# touch_board.net
KiCad netlist of a schematic drawn in EAGLE
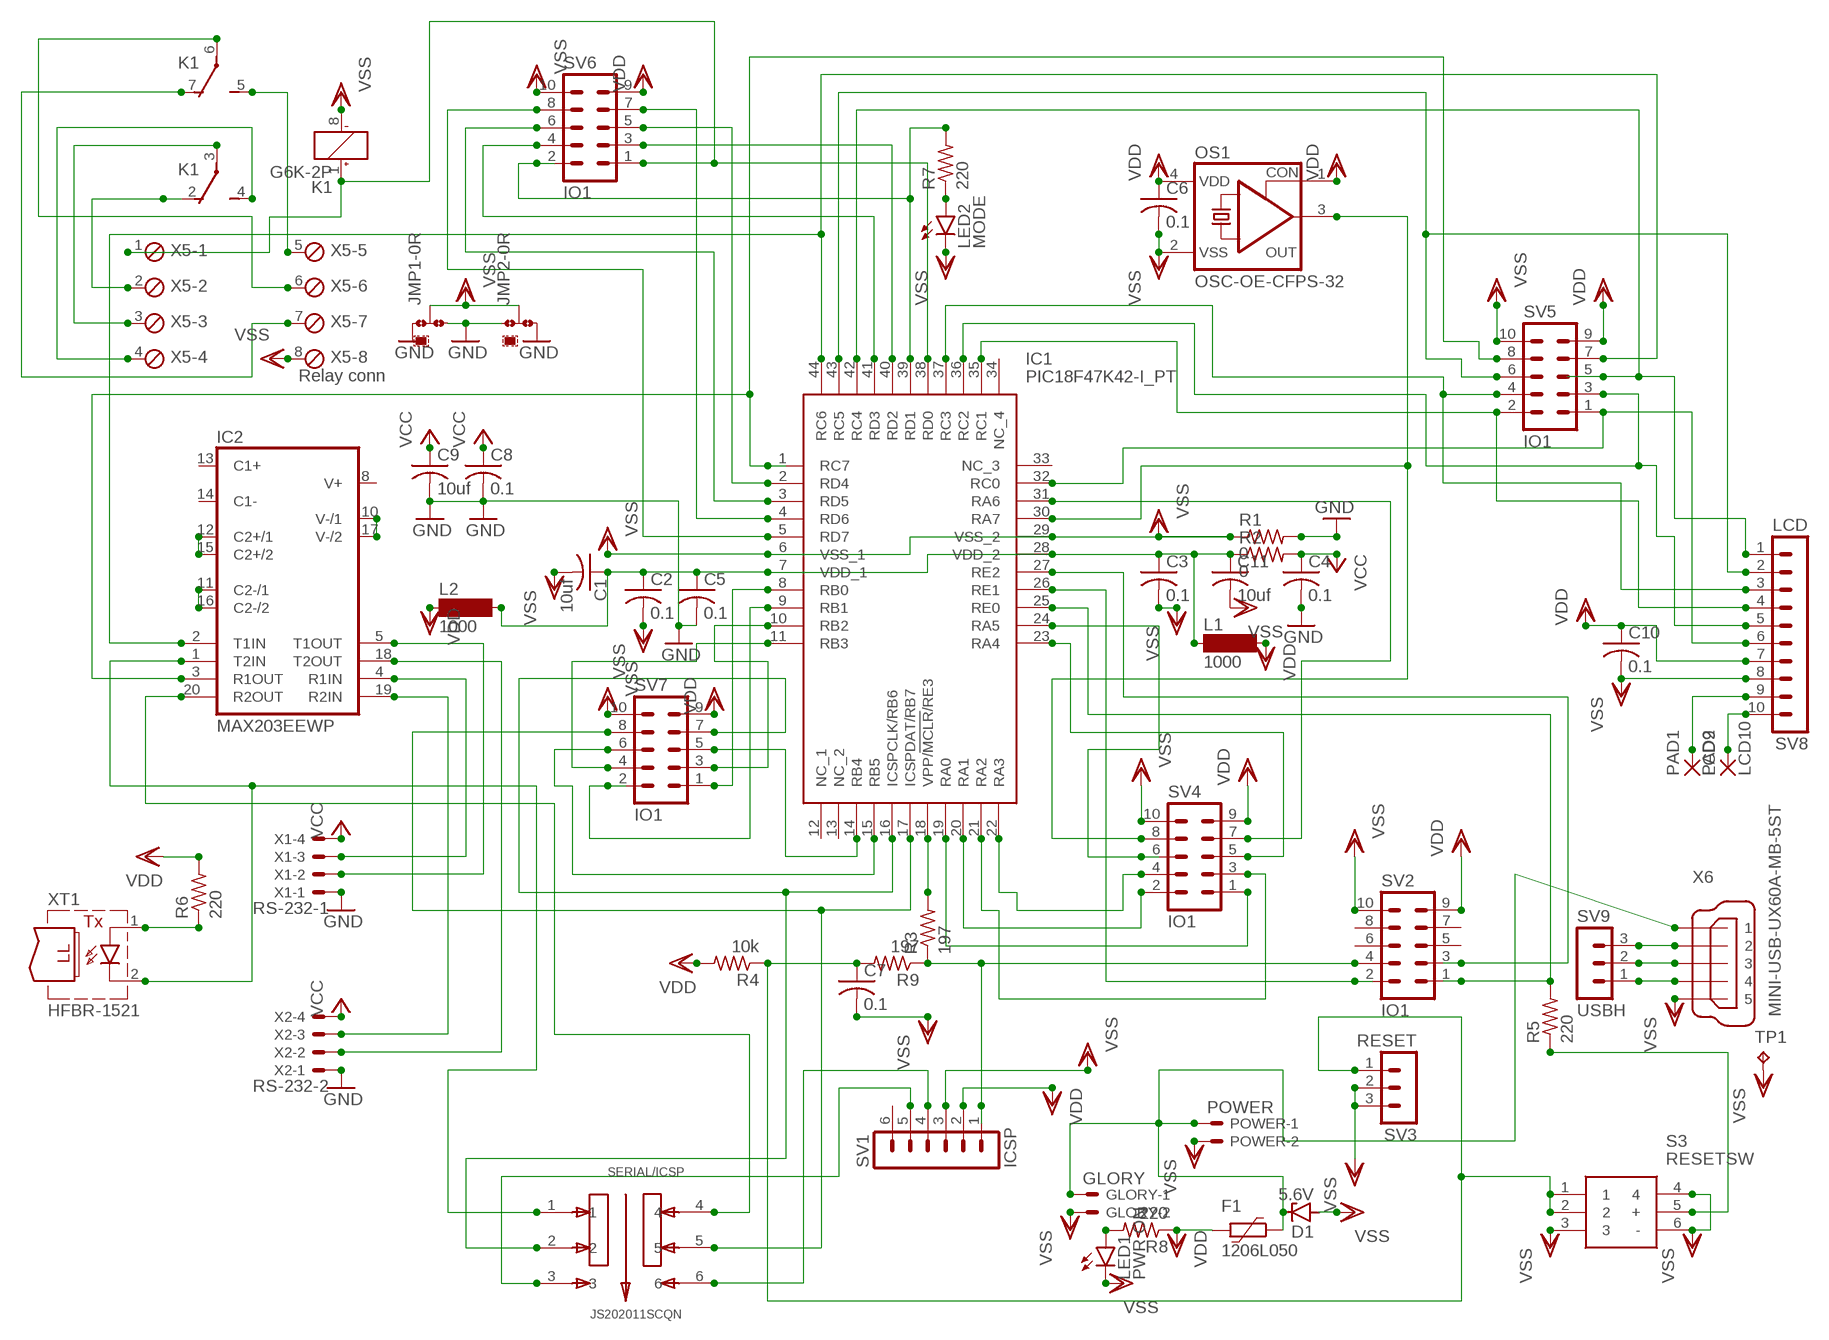
[diagram p0: schematic, sheet 1]

(export (version "E")
  (design (tool "Eeschema 10.0.6"))
  (components
    (comp (ref "C1")
      (value "10uf")
      (footprint "eagle-import:C0805")
      (libsource (lib "eagle-import") (part "C-USC0805"))
    )
    (comp (ref "C2")
      (value "0.1")
      (footprint "eagle-import:C0805")
      (libsource (lib "eagle-import") (part "C-USC0805"))
    )
    (comp (ref "C3")
      (value "0.1")
      (footprint "eagle-import:C0805")
      (libsource (lib "eagle-import") (part "C-USC0805"))
    )
    (comp (ref "C4")
      (value "0.1")
      (footprint "eagle-import:C0805")
      (libsource (lib "eagle-import") (part "C-USC0805"))
    )
    (comp (ref "C5")
      (value "0.1")
      (footprint "eagle-import:C0805")
      (libsource (lib "eagle-import") (part "C-USC0805"))
    )
    (comp (ref "C6")
      (value "0.1")
      (footprint "eagle-import:C0805")
      (libsource (lib "eagle-import") (part "C-USC0805"))
    )
    (comp (ref "C7")
      (value "0.1")
      (footprint "eagle-import:C0805")
      (libsource (lib "eagle-import") (part "C-USC0805"))
    )
    (comp (ref "C8")
      (value "0.1")
      (footprint "eagle-import:C0805")
      (libsource (lib "eagle-import") (part "C-USC0805"))
    )
    (comp (ref "C9")
      (value "10uf")
      (footprint "eagle-import:C0805")
      (libsource (lib "eagle-import") (part "C-USC0805"))
    )
    (comp (ref "C10")
      (value "0.1")
      (footprint "eagle-import:C0805")
      (libsource (lib "eagle-import") (part "C-USC0805"))
    )
    (comp (ref "C11")
      (value "10uf")
      (footprint "eagle-import:C0805")
      (libsource (lib "eagle-import") (part "C-USC0805"))
    )
    (comp (ref "D1")
      (value "5.6V")
      (footprint "eagle-import:ZDIO-7.5")
      (libsource (lib "eagle-import") (part "ZENER-DIODEZD-7.5"))
    )
    (comp (ref "F1")
      (value "1206L050")
      (footprint "eagle-import:1206L")
      (fields (field (name "MF") "Littelfuse"))
      (libsource (lib "eagle-import") (part "?1206L050"))
    )
    (comp (ref "GLORY")
      (value "GLORY")
      (footprint "eagle-import:22-23-2021")
      (fields (field (name "MF") "MOLEX") (field (name "MPN") "22-23-2021"))
      (libsource (lib "eagle-import") (part "22-23-2021"))
    )
    (comp (ref "IC1")
      (value "PIC18F47K42-I_PT")
      (footprint "eagle-import:QFP80P1200X1200X120-44N")
      (fields
        (field (name "MANUFACTURER_PART_NUMBER") "PIC18F47K42-I/PT")
        (field (name "MOUSER_PART_NUMBER") "579-PIC18F47K42-I/PT")
      )
      (libsource (lib "eagle-import") (part "PIC18F47K42-I_PT"))
    )
    (comp (ref "IC2")
      (value "MAX203EEWP")
      (footprint "eagle-import:SO20L")
      (libsource (lib "eagle-import") (part "MAX203WPEE"))
    )
    (comp (ref "JMP1")
      (value "0R-JUMPA")
      (footprint "eagle-import:A0R-JMP")
      (libsource (lib "eagle-import") (part "0R-JUMPA"))
    )
    (comp (ref "JMP2")
      (value "0R-JUMPA")
      (footprint "eagle-import:A0R-JMP")
      (libsource (lib "eagle-import") (part "0R-JUMPA"))
    )
    (comp (ref "K1")
      (value "G6K-2P")
      (footprint "eagle-import:G6K-2P")
      (fields (field (name "MF") "OMRON COMPONENTS USA") (field (name "MPN") "G6K-2P DC3"))
      (libsource (lib "eagle-import") (part "G6K-2P"))
    )
    (comp (ref "L1")
      (value "1000")
      (footprint "eagle-import:SM-1206")
      (libsource (lib "eagle-import") (part "SM-1206"))
    )
    (comp (ref "L2")
      (value "1000")
      (footprint "eagle-import:SM-1206")
      (libsource (lib "eagle-import") (part "SM-1206"))
    )
    (comp (ref "LED1")
      (value "PWR ON")
      (footprint "eagle-import:CHIPLED_1206")
      (libsource (lib "eagle-import") (part "LEDCHIPLED_1206"))
    )
    (comp (ref "LED2")
      (value "MODE")
      (footprint "eagle-import:CHIPLED_1206")
      (libsource (lib "eagle-import") (part "LEDCHIPLED_1206"))
    )
    (comp (ref "OS1")
      (value "OSC-OE-CFPS-32")
      (footprint "eagle-import:7.2X5.2-4-PAD")
      (libsource (lib "eagle-import") (part "OSC-OE-CFPS-32"))
    )
    (comp (ref "PAD1")
      (value "LCD9")
      (footprint "eagle-import:SMD1,27-2,54")
      (libsource (lib "eagle-import") (part "SMD2"))
    )
    (comp (ref "PAD2")
      (value "LCD10")
      (footprint "eagle-import:SMD1,27-2,54")
      (libsource (lib "eagle-import") (part "SMD2"))
    )
    (comp (ref "POWER")
      (value "POWER")
      (footprint "eagle-import:22-23-2021")
      (fields (field (name "MF") "MOLEX") (field (name "MPN") "22-23-2021"))
      (libsource (lib "eagle-import") (part "22-23-2021"))
    )
    (comp (ref "R1")
      (value "0")
      (footprint "eagle-import:R0805")
      (libsource (lib "eagle-import") (part "R-US_R0805"))
    )
    (comp (ref "R2")
      (value "0")
      (footprint "eagle-import:R0805")
      (libsource (lib "eagle-import") (part "R-US_R0805"))
    )
    (comp (ref "R3")
      (value "197")
      (footprint "eagle-import:R0805")
      (libsource (lib "eagle-import") (part "R-US_R0805"))
    )
    (comp (ref "R4")
      (value "10k")
      (footprint "eagle-import:R0805")
      (libsource (lib "eagle-import") (part "R-US_R0805"))
    )
    (comp (ref "R5")
      (value "220")
      (footprint "eagle-import:R0805")
      (libsource (lib "eagle-import") (part "R-US_R0805"))
    )
    (comp (ref "R6")
      (value "220")
      (footprint "eagle-import:R0805")
      (libsource (lib "eagle-import") (part "R-US_R0805"))
    )
    (comp (ref "R7")
      (value "220")
      (footprint "eagle-import:R0805")
      (libsource (lib "eagle-import") (part "R-US_R0805"))
    )
    (comp (ref "R8")
      (value "220")
      (footprint "eagle-import:R0805")
      (libsource (lib "eagle-import") (part "R-US_R0805"))
    )
    (comp (ref "R9")
      (value "197")
      (footprint "eagle-import:R0805")
      (libsource (lib "eagle-import") (part "R-US_R0805"))
    )
    (comp (ref "S3")
      (value "RESETSW")
      (footprint "eagle-import:B3W-9_1-LED")
      (fields
        (field (name "MANUFACTURER_PART_NUMBER") "B3W-9000-Y1N")
        (field (name "MOUSER_PART_NUMBER") "653-B3W-9000-Y1N")
        (field (name "RS_PART_NUMBER") "0492777P")
      )
      (libsource (lib "eagle-import") (part "B3W-9000-Y1N"))
    )
    (comp (ref "SERIAL/ICSP")
      (value "JS202011SCQN")
      (footprint "eagle-import:SW_JS202011SCQN")
      (fields (field (name "MF") "C&K"))
      (libsource (lib "eagle-import") (part "JS202011SCQN"))
    )
    (comp (ref "SV1")
      (value "ICSP")
      (footprint "eagle-import:MA06-1")
      (libsource (lib "eagle-import") (part "MA06-1"))
    )
    (comp (ref "SV2")
      (value "IO1")
      (footprint "eagle-import:MA05-2")
      (libsource (lib "eagle-import") (part "MA05-2"))
    )
    (comp (ref "SV3")
      (value "RESET")
      (footprint "eagle-import:MA03-1")
      (libsource (lib "eagle-import") (part "MA03-1"))
    )
    (comp (ref "SV4")
      (value "IO1")
      (footprint "eagle-import:MA05-2")
      (libsource (lib "eagle-import") (part "MA05-2"))
    )
    (comp (ref "SV5")
      (value "IO1")
      (footprint "eagle-import:MA05-2")
      (libsource (lib "eagle-import") (part "MA05-2"))
    )
    (comp (ref "SV6")
      (value "IO1")
      (footprint "eagle-import:MA05-2")
      (libsource (lib "eagle-import") (part "MA05-2"))
    )
    (comp (ref "SV7")
      (value "IO1")
      (footprint "eagle-import:MA05-2")
      (libsource (lib "eagle-import") (part "MA05-2"))
    )
    (comp (ref "SV8")
      (value "LCD")
      (footprint "eagle-import:MA10-1")
      (libsource (lib "eagle-import") (part "MA10-1"))
    )
    (comp (ref "SV9")
      (value "USBH")
      (footprint "eagle-import:MA03-1")
      (libsource (lib "eagle-import") (part "MA03-1"))
    )
    (comp (ref "TP1")
      (value "TPB1,27")
      (footprint "eagle-import:B1,27")
      (libsource (lib "eagle-import") (part "TPB1,27"))
    )
    (comp (ref "X1")
      (value "RS-232-1")
      (footprint "eagle-import:22-23-2041")
      (fields (field (name "MF") "MOLEX") (field (name "MPN") "22-23-2041"))
      (libsource (lib "eagle-import") (part "22-23-2041"))
    )
    (comp (ref "X2")
      (value "RS-232-2")
      (footprint "eagle-import:22-23-2041")
      (fields (field (name "MF") "MOLEX") (field (name "MPN") "22-23-2041"))
      (libsource (lib "eagle-import") (part "22-23-2041"))
    )
    (comp (ref "X5")
      (value "Relay conn")
      (footprint "eagle-import:8POL254")
      (libsource (lib "eagle-import") (part "MPT8"))
    )
    (comp (ref "X6")
      (value "MINI-USB-UX60A-MB-5ST")
      (footprint "eagle-import:UX60A-MB-5ST")
      (libsource (lib "eagle-import") (part "MINI-USB-UX60A-MB-5ST"))
    )
    (comp (ref "XT1")
      (value "HFBR-1521")
      (footprint "eagle-import:HFBR-15X3")
      (fields (field (name "MF") "AGILENT TECHNOLOGIES"))
      (libsource (lib "eagle-import") (part "HFBR-1521"))
    )
  )
  (nets
    (net (code "1") (name "GND") (class "Default")
      (node (ref "C4") (pin "2") (pinfunction "2_2") (pintype "passive"))
      (node (ref "C5") (pin "2") (pinfunction "2_2") (pintype "passive"))
      (node (ref "C8") (pin "2") (pinfunction "2_2") (pintype "passive"))
      (node (ref "C9") (pin "2") (pinfunction "2_2") (pintype "passive"))
      (node (ref "JMP1") (pin "1") (pinfunction "1_1") (pintype "passive"))
      (node (ref "JMP1") (pin "3") (pinfunction "3_3") (pintype "passive"))
      (node (ref "JMP2") (pin "1") (pinfunction "1_1") (pintype "passive"))
      (node (ref "JMP2") (pin "3") (pinfunction "3_3") (pintype "passive"))
      (node (ref "R1") (pin "2") (pinfunction "2_2") (pintype "passive"))
      (node (ref "X1") (pin "1") (pinfunction "S_1") (pintype "passive"))
      (node (ref "X2") (pin "1") (pinfunction "S_1") (pintype "passive"))
    )
    (net (code "2") (name "Net-(C7-Pad1)") (class "Default")
      (node (ref "C7") (pin "1") (pinfunction "1_1") (pintype "passive"))
      (node (ref "R4") (pin "1") (pinfunction "1_1") (pintype "passive"))
      (node (ref "R9") (pin "2") (pinfunction "2_2") (pintype "passive"))
      (node (ref "S3") (pin "1") (pinfunction "1_1") (pintype "bidirectional"))
      (node (ref "S3") (pin "2") (pinfunction "2_2") (pintype "bidirectional"))
      (node (ref "SV3") (pin "1") (pinfunction "1_1") (pintype "passive"))
    )
    (net (code "3") (name "Net-(GLORYA-S)") (class "Default")
      (node (ref "D1") (pin "C") (pinfunction "C_C") (pintype "passive"))
      (node (ref "F1") (pin "1") (pinfunction "1_1") (pintype "passive"))
      (node (ref "GLORY") (pin "1") (pinfunction "S_1") (pintype "passive"))
      (node (ref "POWER") (pin "1") (pinfunction "S_1") (pintype "passive"))
      (node (ref "X6") (pin "1") (pinfunction "1_1") (pintype "input"))
    )
    (net (code "4") (name "Net-(IC1-ICSPCLK{slash}RB6)") (class "Default")
      (node (ref "IC1") (pin "16") (pinfunction "ICSPCLK/RB6_16") (pintype "bidirectional"))
      (node (ref "SERIAL/ICSP") (pin "2") (pinfunction "2_2") (pintype "passive"))
      (node (ref "SV7") (pin "7") (pinfunction "7_7") (pintype "passive"))
    )
    (net (code "5") (name "Net-(IC1-ICSPDAT{slash}RB7)") (class "Default")
      (node (ref "IC1") (pin "17") (pinfunction "ICSPDAT/RB7_17") (pintype "bidirectional"))
      (node (ref "SERIAL/ICSP") (pin "5") (pinfunction "5_5") (pintype "passive"))
      (node (ref "SV7") (pin "8") (pinfunction "8_8") (pintype "passive"))
    )
    (net (code "6") (name "Net-(IC1-RA0)") (class "Default")
      (node (ref "IC1") (pin "19") (pinfunction "RA0_19") (pintype "bidirectional"))
      (node (ref "SV4") (pin "1") (pinfunction "1_1") (pintype "passive"))
    )
    (net (code "7") (name "Net-(IC1-RA1)") (class "Default")
      (node (ref "IC1") (pin "20") (pinfunction "RA1_20") (pintype "bidirectional"))
      (node (ref "SV4") (pin "2") (pinfunction "2_2") (pintype "passive"))
    )
    (net (code "8") (name "Net-(IC1-RA2)") (class "Default")
      (node (ref "IC1") (pin "21") (pinfunction "RA2_21") (pintype "bidirectional"))
      (node (ref "SV4") (pin "3") (pinfunction "3_3") (pintype "passive"))
    )
    (net (code "9") (name "Net-(IC1-RA3)") (class "Default")
      (node (ref "IC1") (pin "22") (pinfunction "RA3_22") (pintype "bidirectional"))
      (node (ref "SV4") (pin "4") (pinfunction "4_4") (pintype "passive"))
    )
    (net (code "10") (name "Net-(IC1-RA4)") (class "Default")
      (node (ref "IC1") (pin "23") (pinfunction "RA4_23") (pintype "bidirectional"))
      (node (ref "SV4") (pin "5") (pinfunction "5_5") (pintype "passive"))
    )
    (net (code "11") (name "Net-(IC1-RA5)") (class "Default")
      (node (ref "IC1") (pin "24") (pinfunction "RA5_24") (pintype "bidirectional"))
      (node (ref "SV4") (pin "6") (pinfunction "6_6") (pintype "passive"))
    )
    (net (code "12") (name "Net-(IC1-RA6)") (class "Default")
      (node (ref "IC1") (pin "31") (pinfunction "RA6_31") (pintype "bidirectional"))
      (node (ref "SV4") (pin "7") (pinfunction "7_7") (pintype "passive"))
    )
    (net (code "13") (name "Net-(IC1-RA7)") (class "Default")
      (node (ref "IC1") (pin "30") (pinfunction "RA7_30") (pintype "bidirectional"))
      (node (ref "OS1") (pin "3") (pinfunction "OUT_3") (pintype "output"))
      (node (ref "SV4") (pin "8") (pinfunction "8_8") (pintype "passive"))
    )
    (net (code "14") (name "Net-(IC1-RB0)") (class "Default")
      (node (ref "IC1") (pin "8") (pinfunction "RB0_8") (pintype "bidirectional"))
      (node (ref "SV7") (pin "1") (pinfunction "1_1") (pintype "passive"))
    )
    (net (code "15") (name "Net-(IC1-RB1)") (class "Default")
      (node (ref "IC1") (pin "9") (pinfunction "RB1_9") (pintype "bidirectional"))
      (node (ref "SV7") (pin "2") (pinfunction "2_2") (pintype "passive"))
    )
    (net (code "16") (name "Net-(IC1-RB2)") (class "Default")
      (node (ref "IC1") (pin "10") (pinfunction "RB2_10") (pintype "bidirectional"))
      (node (ref "SV7") (pin "3") (pinfunction "3_3") (pintype "passive"))
    )
    (net (code "17") (name "Net-(IC1-RB3)") (class "Default")
      (node (ref "IC1") (pin "11") (pinfunction "RB3_11") (pintype "bidirectional"))
      (node (ref "SV7") (pin "4") (pinfunction "4_4") (pintype "passive"))
    )
    (net (code "18") (name "Net-(IC1-RB4)") (class "Default")
      (node (ref "IC1") (pin "14") (pinfunction "RB4_14") (pintype "bidirectional"))
      (node (ref "SV7") (pin "5") (pinfunction "5_5") (pintype "passive"))
    )
    (net (code "19") (name "Net-(IC1-RB5)") (class "Default")
      (node (ref "IC1") (pin "15") (pinfunction "RB5_15") (pintype "bidirectional"))
      (node (ref "SV7") (pin "6") (pinfunction "6_6") (pintype "passive"))
    )
    (net (code "20") (name "Net-(IC1-RC0)") (class "Default")
      (node (ref "IC1") (pin "32") (pinfunction "RC0_32") (pintype "bidirectional"))
      (node (ref "SV5") (pin "1") (pinfunction "1_1") (pintype "passive"))
      (node (ref "SV8") (pin "6") (pinfunction "6_6") (pintype "passive"))
    )
    (net (code "21") (name "Net-(IC1-RC1)") (class "Default")
      (node (ref "IC1") (pin "35") (pinfunction "RC1_35") (pintype "bidirectional"))
      (node (ref "SV5") (pin "2") (pinfunction "2_2") (pintype "passive"))
      (node (ref "SV8") (pin "4") (pinfunction "4_4") (pintype "passive"))
    )
    (net (code "22") (name "Net-(IC1-RC2)") (class "Default")
      (node (ref "IC1") (pin "36") (pinfunction "RC2_36") (pintype "bidirectional"))
      (node (ref "SV5") (pin "3") (pinfunction "3_3") (pintype "passive"))
      (node (ref "SV8") (pin "5") (pinfunction "5_5") (pintype "passive"))
    )
    (net (code "23") (name "Net-(IC1-RC3)") (class "Default")
      (node (ref "IC1") (pin "37") (pinfunction "RC3_37") (pintype "bidirectional"))
      (node (ref "SV5") (pin "4") (pinfunction "4_4") (pintype "passive"))
      (node (ref "SV8") (pin "3") (pinfunction "3_3") (pintype "passive"))
    )
    (net (code "24") (name "Net-(IC1-RC4)") (class "Default")
      (node (ref "IC1") (pin "42") (pinfunction "RC4_42") (pintype "bidirectional"))
      (node (ref "SV5") (pin "5") (pinfunction "5_5") (pintype "passive"))
      (node (ref "SV8") (pin "1") (pinfunction "1_1") (pintype "passive"))
    )
    (net (code "25") (name "Net-(IC1-RC5)") (class "Default")
      (node (ref "IC1") (pin "43") (pinfunction "RC5_43") (pintype "bidirectional"))
      (node (ref "SV5") (pin "6") (pinfunction "6_6") (pintype "passive"))
      (node (ref "SV8") (pin "2") (pinfunction "2_2") (pintype "passive"))
    )
    (net (code "26") (name "Net-(IC1-RC6)") (class "Default")
      (node (ref "IC1") (pin "44") (pinfunction "RC6_44") (pintype "bidirectional"))
      (node (ref "IC2") (pin "2") (pinfunction "T1IN_2") (pintype "input"))
      (node (ref "SV5") (pin "7") (pinfunction "7_7") (pintype "passive"))
    )
    (net (code "27") (name "Net-(IC1-RC7)") (class "Default")
      (node (ref "IC1") (pin "1") (pinfunction "RC7_1") (pintype "bidirectional"))
      (node (ref "IC2") (pin "3") (pinfunction "R1OUT_3") (pintype "output"))
      (node (ref "SV5") (pin "8") (pinfunction "8_8") (pintype "passive"))
    )
    (net (code "28") (name "Net-(IC1-RD0)") (class "Default")
      (node (ref "IC1") (pin "38") (pinfunction "RD0_38") (pintype "bidirectional"))
      (node (ref "K1") (pin "1") (pinfunction "+_1") (pintype "passive"))
      (node (ref "SV6") (pin "1") (pinfunction "1_1") (pintype "passive"))
      (node (ref "X5") (pin "1") (pinfunction "1_1") (pintype "passive"))
    )
    (net (code "29") (name "Net-(IC1-RD1)") (class "Default")
      (node (ref "IC1") (pin "39") (pinfunction "RD1_39") (pintype "bidirectional"))
      (node (ref "R7") (pin "2") (pinfunction "2_2") (pintype "passive"))
      (node (ref "SV6") (pin "2") (pinfunction "2_2") (pintype "passive"))
    )
    (net (code "30") (name "Net-(IC1-RD2)") (class "Default")
      (node (ref "IC1") (pin "40") (pinfunction "RD2_40") (pintype "bidirectional"))
      (node (ref "SV6") (pin "3") (pinfunction "3_3") (pintype "passive"))
    )
    (net (code "31") (name "Net-(IC1-RD3)") (class "Default")
      (node (ref "IC1") (pin "41") (pinfunction "RD3_41") (pintype "bidirectional"))
      (node (ref "SV6") (pin "4") (pinfunction "4_4") (pintype "passive"))
    )
    (net (code "32") (name "Net-(IC1-RD4)") (class "Default")
      (node (ref "IC1") (pin "2") (pinfunction "RD4_2") (pintype "bidirectional"))
      (node (ref "SV6") (pin "5") (pinfunction "5_5") (pintype "passive"))
    )
    (net (code "33") (name "Net-(IC1-RD5)") (class "Default")
      (node (ref "IC1") (pin "3") (pinfunction "RD5_3") (pintype "bidirectional"))
      (node (ref "SV6") (pin "6") (pinfunction "6_6") (pintype "passive"))
    )
    (net (code "34") (name "Net-(IC1-RD6)") (class "Default")
      (node (ref "IC1") (pin "4") (pinfunction "RD6_4") (pintype "bidirectional"))
      (node (ref "SV6") (pin "7") (pinfunction "7_7") (pintype "passive"))
    )
    (net (code "35") (name "Net-(IC1-RD7)") (class "Default")
      (node (ref "IC1") (pin "5") (pinfunction "RD7_5") (pintype "bidirectional"))
      (node (ref "SV6") (pin "8") (pinfunction "8_8") (pintype "passive"))
    )
    (net (code "36") (name "Net-(IC1-RE0)") (class "Default")
      (node (ref "IC1") (pin "25") (pinfunction "RE0_25") (pintype "bidirectional"))
      (node (ref "R5") (pin "2") (pinfunction "2_2") (pintype "passive"))
      (node (ref "SV2") (pin "1") (pinfunction "1_1") (pintype "passive"))
    )
    (net (code "37") (name "Net-(IC1-RE1)") (class "Default")
      (node (ref "IC1") (pin "26") (pinfunction "RE1_26") (pintype "bidirectional"))
      (node (ref "SV2") (pin "2") (pinfunction "2_2") (pintype "passive"))
    )
    (net (code "38") (name "Net-(IC1-RE2)") (class "Default")
      (node (ref "IC1") (pin "27") (pinfunction "RE2_27") (pintype "bidirectional"))
      (node (ref "SV2") (pin "3") (pinfunction "3_3") (pintype "passive"))
    )
    (net (code "39") (name "Net-(IC1-VDD_1)") (class "Default")
      (node (ref "C1") (pin "1") (pinfunction "1_1") (pintype "passive"))
      (node (ref "C11") (pin "1") (pinfunction "1_1") (pintype "passive"))
      (node (ref "C2") (pin "1") (pinfunction "1_1") (pintype "passive"))
      (node (ref "C3") (pin "1") (pinfunction "1_1") (pintype "passive"))
      (node (ref "C5") (pin "1") (pinfunction "1_1") (pintype "passive"))
      (node (ref "IC1") (pin "28") (pinfunction "VDD_2_28") (pintype "bidirectional"))
      (node (ref "IC1") (pin "7") (pinfunction "VDD_1_7") (pintype "bidirectional"))
      (node (ref "L1") (pin "1") (pinfunction "1_1") (pintype "passive"))
      (node (ref "L2") (pin "2") (pinfunction "2_2") (pintype "passive"))
      (node (ref "R2") (pin "1") (pinfunction "1_1") (pintype "passive"))
    )
    (net (code "40") (name "Net-(IC1-VPP{slash}~{MCLR}{slash}RE3)") (class "Default")
      (node (ref "IC1") (pin "18") (pinfunction "VPP/~{MCLR}/RE3_18") (pintype "bidirectional"))
      (node (ref "R3") (pin "2") (pinfunction "2_2") (pintype "passive"))
    )
    (net (code "41") (name "Net-(IC2A-C2+{slash}1)") (class "Default")
      (node (ref "IC2") (pin "12") (pinfunction "C2+/1_12") (pintype "passive"))
      (node (ref "IC2") (pin "15") (pinfunction "C2+/2_15") (pintype "passive"))
    )
    (net (code "42") (name "Net-(IC2A-C2-{slash}1)") (class "Default")
      (node (ref "IC2") (pin "11") (pinfunction "C2-/1_11") (pintype "passive"))
      (node (ref "IC2") (pin "16") (pinfunction "C2-/2_16") (pintype "passive"))
    )
    (net (code "43") (name "Net-(IC2A-R1IN)") (class "Default")
      (node (ref "IC2") (pin "4") (pinfunction "R1IN_4") (pintype "input"))
      (node (ref "X1") (pin "3") (pinfunction "S_3") (pintype "passive"))
    )
    (net (code "44") (name "Net-(IC2A-R2IN)") (class "Default")
      (node (ref "IC2") (pin "19") (pinfunction "R2IN_19") (pintype "input"))
      (node (ref "X2") (pin "3") (pinfunction "S_3") (pintype "passive"))
    )
    (net (code "45") (name "Net-(IC2A-R2OUT)") (class "Default")
      (node (ref "IC2") (pin "20") (pinfunction "R2OUT_20") (pintype "output"))
      (node (ref "SERIAL/ICSP") (pin "4") (pinfunction "4_4") (pintype "passive"))
    )
    (net (code "46") (name "Net-(IC2A-T1OUT)") (class "Default")
      (node (ref "IC2") (pin "5") (pinfunction "T1OUT_5") (pintype "output"))
      (node (ref "X1") (pin "2") (pinfunction "S_2") (pintype "passive"))
    )
    (net (code "47") (name "Net-(IC2A-T2IN)") (class "Default")
      (node (ref "IC2") (pin "1") (pinfunction "T2IN_1") (pintype "input"))
      (node (ref "SERIAL/ICSP") (pin "1") (pinfunction "1_1") (pintype "passive"))
      (node (ref "XT1") (pin "2") (pinfunction "C_2") (pintype "passive"))
    )
    (net (code "48") (name "Net-(IC2A-T2OUT)") (class "Default")
      (node (ref "IC2") (pin "18") (pinfunction "T2OUT_18") (pintype "output"))
      (node (ref "X2") (pin "2") (pinfunction "S_2") (pintype "passive"))
    )
    (net (code "49") (name "Net-(IC2A-V-{slash}1)") (class "Default")
      (node (ref "IC2") (pin "10") (pinfunction "V-/1_10") (pintype "passive"))
      (node (ref "IC2") (pin "17") (pinfunction "V-/2_17") (pintype "passive"))
    )
    (net (code "50") (name "Net-(K1B-O)") (class "Default")
      (node (ref "K1") (pin "2") (pinfunction "O_2") (pintype "passive"))
      (node (ref "X5") (pin "2") (pinfunction "1_2") (pintype "passive"))
    )
    (net (code "51") (name "Net-(K1B-P)") (class "Default")
      (node (ref "K1") (pin "3") (pinfunction "P_3") (pintype "passive"))
      (node (ref "X5") (pin "3") (pinfunction "1_3") (pintype "passive"))
    )
    (net (code "52") (name "Net-(K1B-S)") (class "Default")
      (node (ref "K1") (pin "4") (pinfunction "S_4") (pintype "passive"))
      (node (ref "X5") (pin "4") (pinfunction "1_4") (pintype "passive"))
    )
    (net (code "53") (name "Net-(K1C-O)") (class "Default")
      (node (ref "K1") (pin "7") (pinfunction "O_7") (pintype "passive"))
      (node (ref "X5") (pin "7") (pinfunction "1_7") (pintype "passive"))
    )
    (net (code "54") (name "Net-(K1C-P)") (class "Default")
      (node (ref "K1") (pin "6") (pinfunction "P_6") (pintype "passive"))
      (node (ref "X5") (pin "6") (pinfunction "1_6") (pintype "passive"))
    )
    (net (code "55") (name "Net-(K1C-S)") (class "Default")
      (node (ref "K1") (pin "5") (pinfunction "S_5") (pintype "passive"))
      (node (ref "X5") (pin "5") (pinfunction "1_5") (pintype "passive"))
    )
    (net (code "56") (name "Net-(LED1-PadA)") (class "Default")
      (node (ref "LED1") (pin "A") (pinfunction "A_A") (pintype "passive"))
      (node (ref "R8") (pin "2") (pinfunction "2_2") (pintype "passive"))
    )
    (net (code "57") (name "Net-(LED2-PadA)") (class "Default")
      (node (ref "LED2") (pin "A") (pinfunction "A_A") (pintype "passive"))
      (node (ref "R7") (pin "1") (pinfunction "1_1") (pintype "passive"))
    )
    (net (code "58") (name "Net-(PAD1-P)") (class "Default")
      (node (ref "PAD1") (pin "1") (pinfunction "P_1") (pintype "passive"))
      (node (ref "SV8") (pin "9") (pinfunction "9_9") (pintype "passive"))
    )
    (net (code "59") (name "Net-(PAD2-P)") (class "Default")
      (node (ref "PAD2") (pin "1") (pinfunction "P_1") (pintype "passive"))
      (node (ref "SV8") (pin "10") (pinfunction "10_10") (pintype "passive"))
    )
    (net (code "60") (name "Net-(R3-Pad1)") (class "Default")
      (node (ref "R3") (pin "1") (pinfunction "1_1") (pintype "passive"))
      (node (ref "R9") (pin "1") (pinfunction "1_1") (pintype "passive"))
      (node (ref "SV1") (pin "1") (pinfunction "1_1") (pintype "passive"))
      (node (ref "SV2") (pin "4") (pinfunction "4_4") (pintype "passive"))
    )
    (net (code "61") (name "Net-(S3-+)") (class "Default")
      (node (ref "R5") (pin "1") (pinfunction "1_1") (pintype "passive"))
      (node (ref "S3") (pin "5") (pinfunction "+_5") (pintype "bidirectional"))
    )
    (net (code "62") (name "Net-(SERIAL/ICSP-Pad3)") (class "Default")
      (node (ref "SERIAL/ICSP") (pin "3") (pinfunction "3_3") (pintype "passive"))
      (node (ref "SV1") (pin "5") (pinfunction "5_5") (pintype "passive"))
    )
    (net (code "63") (name "Net-(SERIAL/ICSP-Pad6)") (class "Default")
      (node (ref "SERIAL/ICSP") (pin "6") (pinfunction "6_6") (pintype "passive"))
      (node (ref "SV1") (pin "4") (pinfunction "4_4") (pintype "passive"))
    )
    (net (code "64") (name "Net-(SV9-Pad1)") (class "Default")
      (node (ref "SV9") (pin "1") (pinfunction "1_1") (pintype "passive"))
      (node (ref "X6") (pin "4") (pinfunction "4_4") (pintype "input"))
    )
    (net (code "65") (name "Net-(SV9-Pad2)") (class "Default")
      (node (ref "SV9") (pin "2") (pinfunction "2_2") (pintype "passive"))
      (node (ref "X6") (pin "3") (pinfunction "3_3") (pintype "input"))
    )
    (net (code "66") (name "Net-(SV9-Pad3)") (class "Default")
      (node (ref "SV9") (pin "3") (pinfunction "3_3") (pintype "passive"))
      (node (ref "X6") (pin "2") (pinfunction "2_2") (pintype "input"))
    )
    (net (code "67") (name "Net-(XT1-A)") (class "Default")
      (node (ref "R6") (pin "1") (pinfunction "1_1") (pintype "passive"))
      (node (ref "XT1") (pin "1") (pinfunction "A_1") (pintype "passive"))
    )
    (net (code "68") (name "VCC") (class "Default")
      (node (ref "C4") (pin "1") (pinfunction "1_1") (pintype "passive"))
      (node (ref "C8") (pin "1") (pinfunction "1_1") (pintype "passive"))
      (node (ref "C9") (pin "1") (pinfunction "1_1") (pintype "passive"))
      (node (ref "R2") (pin "2") (pinfunction "2_2") (pintype "passive"))
      (node (ref "X1") (pin "4") (pinfunction "S_4") (pintype "passive"))
      (node (ref "X2") (pin "4") (pinfunction "S_4") (pintype "passive"))
    )
    (net (code "69") (name "VDD") (class "Default")
      (node (ref "C10") (pin "1") (pinfunction "1_1") (pintype "passive"))
      (node (ref "C6") (pin "1") (pinfunction "1_1") (pintype "passive"))
      (node (ref "F1") (pin "2") (pinfunction "2_2") (pintype "passive"))
      (node (ref "L1") (pin "2") (pinfunction "2_2") (pintype "passive"))
      (node (ref "L2") (pin "1") (pinfunction "1_1") (pintype "passive"))
      (node (ref "OS1") (pin "1") (pinfunction "CON_1") (pintype "input"))
      (node (ref "OS1") (pin "4") (pinfunction "VDD_4") (pintype "power_in"))
      (node (ref "R4") (pin "2") (pinfunction "2_2") (pintype "passive"))
      (node (ref "R6") (pin "2") (pinfunction "2_2") (pintype "passive"))
      (node (ref "R8") (pin "1") (pinfunction "1_1") (pintype "passive"))
      (node (ref "SV1") (pin "2") (pinfunction "2_2") (pintype "passive"))
      (node (ref "SV2") (pin "9") (pinfunction "9_9") (pintype "passive"))
      (node (ref "SV4") (pin "9") (pinfunction "9_9") (pintype "passive"))
      (node (ref "SV5") (pin "9") (pinfunction "9_9") (pintype "passive"))
      (node (ref "SV6") (pin "9") (pinfunction "9_9") (pintype "passive"))
      (node (ref "SV7") (pin "9") (pinfunction "9_9") (pintype "passive"))
      (node (ref "SV8") (pin "7") (pinfunction "7_7") (pintype "passive"))
    )
    (net (code "70") (name "VSS") (class "Default")
      (node (ref "C1") (pin "2") (pinfunction "2_2") (pintype "passive"))
      (node (ref "C10") (pin "2") (pinfunction "2_2") (pintype "passive"))
      (node (ref "C11") (pin "2") (pinfunction "2_2") (pintype "passive"))
      (node (ref "C2") (pin "2") (pinfunction "2_2") (pintype "passive"))
      (node (ref "C3") (pin "2") (pinfunction "2_2") (pintype "passive"))
      (node (ref "C6") (pin "2") (pinfunction "2_2") (pintype "passive"))
      (node (ref "C7") (pin "2") (pinfunction "2_2") (pintype "passive"))
      (node (ref "D1") (pin "A") (pinfunction "A_A") (pintype "passive"))
      (node (ref "GLORY") (pin "2") (pinfunction "S_2") (pintype "passive"))
      (node (ref "IC1") (pin "29") (pinfunction "VSS_2_29") (pintype "bidirectional"))
      (node (ref "IC1") (pin "6") (pinfunction "VSS_1_6") (pintype "bidirectional"))
      (node (ref "JMP1") (pin "2") (pinfunction "2_2") (pintype "passive"))
      (node (ref "JMP2") (pin "2") (pinfunction "2_2") (pintype "passive"))
      (node (ref "K1") (pin "8") (pinfunction "-_8") (pintype "passive"))
      (node (ref "LED1") (pin "C") (pinfunction "C_C") (pintype "passive"))
      (node (ref "LED2") (pin "C") (pinfunction "C_C") (pintype "passive"))
      (node (ref "OS1") (pin "2") (pinfunction "VSS_2") (pintype "power_in"))
      (node (ref "POWER") (pin "2") (pinfunction "S_2") (pintype "passive"))
      (node (ref "R1") (pin "1") (pinfunction "1_1") (pintype "passive"))
      (node (ref "S3") (pin "3") (pinfunction "3_3") (pintype "bidirectional"))
      (node (ref "S3") (pin "4") (pinfunction "4_4") (pintype "bidirectional"))
      (node (ref "S3") (pin "6") (pinfunction "-_6") (pintype "bidirectional"))
      (node (ref "SV1") (pin "3") (pinfunction "3_3") (pintype "passive"))
      (node (ref "SV2") (pin "10") (pinfunction "10_10") (pintype "passive"))
      (node (ref "SV3") (pin "2") (pinfunction "2_2") (pintype "passive"))
      (node (ref "SV3") (pin "3") (pinfunction "3_3") (pintype "passive"))
      (node (ref "SV4") (pin "10") (pinfunction "10_10") (pintype "passive"))
      (node (ref "SV5") (pin "10") (pinfunction "10_10") (pintype "passive"))
      (node (ref "SV6") (pin "10") (pinfunction "10_10") (pintype "passive"))
      (node (ref "SV7") (pin "10") (pinfunction "10_10") (pintype "passive"))
      (node (ref "SV8") (pin "8") (pinfunction "8_8") (pintype "passive"))
      (node (ref "TP1") (pin "TP") (pinfunction "TP_TP") (pintype "input"))
      (node (ref "X5") (pin "8") (pinfunction "1_8") (pintype "passive"))
      (node (ref "X6") (pin "5") (pinfunction "5_5") (pintype "input"))
    )
    (net (code "71") (name "unconnected-(IC1-NC_1-Pad12)") (class "Default")
      (node (ref "IC1") (pin "12") (pinfunction "NC_1_12") (pintype "bidirectional"))
    )
    (net (code "72") (name "unconnected-(IC1-NC_2-Pad13)") (class "Default")
      (node (ref "IC1") (pin "13") (pinfunction "NC_2_13") (pintype "bidirectional"))
    )
    (net (code "73") (name "unconnected-(IC1-NC_3-Pad33)") (class "Default")
      (node (ref "IC1") (pin "33") (pinfunction "NC_3_33") (pintype "bidirectional"))
    )
    (net (code "74") (name "unconnected-(IC1-NC_4-Pad34)") (class "Default")
      (node (ref "IC1") (pin "34") (pinfunction "NC_4_34") (pintype "bidirectional"))
    )
    (net (code "75") (name "unconnected-(IC2A-C1+-Pad13)") (class "Default")
      (node (ref "IC2") (pin "13") (pinfunction "C1+_13") (pintype "passive"))
    )
    (net (code "76") (name "unconnected-(IC2A-C1--Pad14)") (class "Default")
      (node (ref "IC2") (pin "14") (pinfunction "C1-_14") (pintype "passive"))
    )
    (net (code "77") (name "unconnected-(IC2A-V+-Pad8)") (class "Default")
      (node (ref "IC2") (pin "8") (pinfunction "V+_8") (pintype "passive"))
    )
    (net (code "78") (name "unconnected-(SV1-Pad6)") (class "Default")
      (node (ref "SV1") (pin "6") (pinfunction "6_6") (pintype "passive"))
    )
    (net (code "79") (name "unconnected-(SV2-Pad5)") (class "Default")
      (node (ref "SV2") (pin "5") (pinfunction "5_5") (pintype "passive"))
    )
    (net (code "80") (name "unconnected-(SV2-Pad6)") (class "Default")
      (node (ref "SV2") (pin "6") (pinfunction "6_6") (pintype "passive"))
    )
    (net (code "81") (name "unconnected-(SV2-Pad7)") (class "Default")
      (node (ref "SV2") (pin "7") (pinfunction "7_7") (pintype "passive"))
    )
    (net (code "82") (name "unconnected-(SV2-Pad8)") (class "Default")
      (node (ref "SV2") (pin "8") (pinfunction "8_8") (pintype "passive"))
    )
  )
)
